# AWR2243_QSPI_Flash.net
KiCad netlist of a schematic drawn in Altium Designer
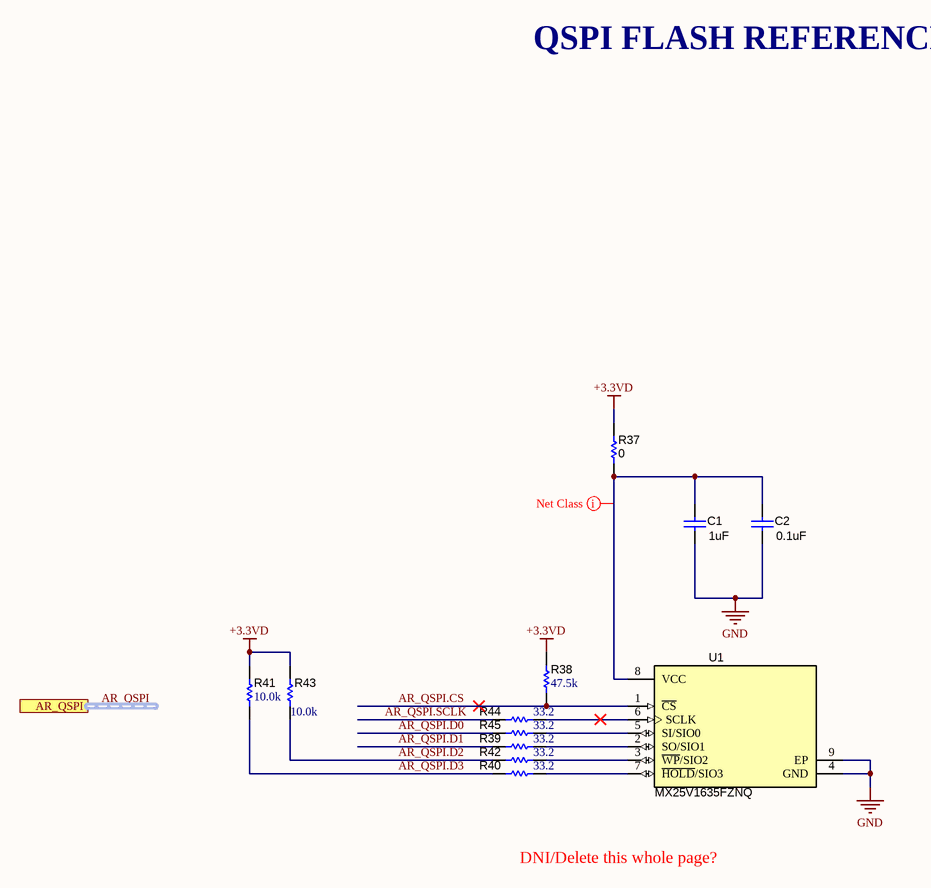
[diagram p0: AWR2243_QSPI_Flash.SchDoc]

(export (version "E")
  (design (tool "Eeschema 10.0.6"))
  (components
    (comp (ref "C1")
      (value "GCM188R71C105KA64D")
      (footprint "0603")
      (description "CAP, CERM, 1 uF, 16 V, +/- 10%, X7R, AEC-Q200 Grade 1, 0603")
      (fields
        (field (name "MANUFACTURER") "MuRata")
        (field (name "VALUEDISPLAYED") "1uF")
        (field (name "PUBLISHER") "Texas Instruments")
      )
      (libsource (lib "Altium Vault - TI") (part "Capacitor"))
    )
    (comp (ref "C2")
      (value "CGA2B3X7R1H104K050BB")
      (footprint "0402L")
      (description "CAP, CERM, 0.1 uF, 50 V, +/- 10%, X7R, AEC-Q200 Grade 1, 0402")
      (fields
        (field (name "MANUFACTURER") "TDK")
        (field (name "VALUEDISPLAYED") "0.1uF")
        (field (name "PUBLISHER") "Texas Instruments")
      )
      (libsource (lib "Altium Vault - TI") (part "Capacitor"))
    )
    (comp (ref "R37")
      (value "ERJ-2GE0R00X")
      (footprint "0402L")
      (description "RES, 0, 5%, 0.063 W, 0402")
      (fields
        (field (name "MANUFACTURER") "Panasonic")
        (field (name "VALUEDISPLAYED") "0")
        (field (name "PUBLISHER") "Texas Instruments")
      )
      (libsource (lib "Altium Vault - TI") (part "Resistor"))
    )
    (comp (ref "R38")
      (value "CRCW040247K5FKED")
      (footprint "0402L")
      (description "RES, 47.5 k, 1%, 0.063 W, AEC-Q200 Grade 0, 0402")
      (fields (field (name "MANUFACTURER") "Vishay-Dale") (field (name "VALUEDISPLAYED") "47.5k"))
      (libsource (lib "Altium Vault - TI") (part "Resistor"))
    )
    (comp (ref "R39")
      (value "CRCW020133R2FNED")
      (footprint "0201_Silk")
      (description "RES, 33.2, 1%, 0.05 W, 0201")
      (fields (field (name "MANUFACTURER") "Vishay-Dale") (field (name "VALUEDISPLAYED") "33.2"))
      (libsource (lib "Altium Vault - TI") (part "Resistor"))
    )
    (comp (ref "R40")
      (value "CRCW020133R2FNED")
      (footprint "0201_Silk")
      (description "RES, 33.2, 1%, 0.05 W, 0201")
      (fields (field (name "MANUFACTURER") "Vishay-Dale") (field (name "VALUEDISPLAYED") "33.2"))
      (libsource (lib "Altium Vault - TI") (part "Resistor"))
    )
    (comp (ref "R41")
      (value "CRCW040210K0FKED")
      (footprint "0402L")
      (description "RES, 10.0 k, 1%, 0.063 W, AEC-Q200 Grade 0, 0402")
      (fields (field (name "MANUFACTURER") "Vishay-Dale") (field (name "VALUEDISPLAYED") "10.0k"))
      (libsource (lib "Altium Vault - TI") (part "Resistor"))
    )
    (comp (ref "R42")
      (value "CRCW020133R2FNED")
      (footprint "0201_Silk")
      (description "RES, 33.2, 1%, 0.05 W, 0201")
      (fields (field (name "MANUFACTURER") "Vishay-Dale") (field (name "VALUEDISPLAYED") "33.2"))
      (libsource (lib "Altium Vault - TI") (part "Resistor"))
    )
    (comp (ref "R43")
      (value "CRCW040210K0FKED")
      (footprint "0402L")
      (description "RES, 10.0 k, 1%, 0.063 W, AEC-Q200 Grade 0, 0402")
      (fields (field (name "MANUFACTURER") "Vishay-Dale") (field (name "VALUEDISPLAYED") "10.0k"))
      (libsource (lib "Altium Vault - TI") (part "Resistor"))
    )
    (comp (ref "R44")
      (value "CRCW020133R2FNED")
      (footprint "0201_Silk")
      (description "RES, 33.2, 1%, 0.05 W, 0201")
      (fields (field (name "MANUFACTURER") "Vishay-Dale") (field (name "VALUEDISPLAYED") "33.2"))
      (libsource (lib "Altium Vault - TI") (part "Resistor"))
    )
    (comp (ref "R45")
      (value "CRCW020133R2FNED")
      (footprint "0201_Silk")
      (description "RES, 33.2, 1%, 0.05 W, 0201")
      (fields (field (name "MANUFACTURER") "Vishay-Dale") (field (name "VALUEDISPLAYED") "33.2"))
      (libsource (lib "Altium Vault - TI") (part "Resistor"))
    )
    (comp (ref "U1")
      (value "MX25V1635FZNQ")
      (footprint "WSON-8L_6x5MM_EP")
      (description "2.3V-3.6V, 16M-BIT [x 1/x 2/x 4] CMOS FLASH Memory, WSON-8")
      (fields (field (name "MANUFACTURER") "Macronix International Co., LTD"))
      (libsource (lib "Altium Vault - TI") (part "MX25V1635FZ"))
    )
  )
  (nets
    (net (code "2") (name "+3.3VD") (class "Default")
      (node (ref "R37") (pin "1") (pinfunction "1_1") (pintype "passive"))
      (node (ref "R38") (pin "2") (pinfunction "2_2") (pintype "passive"))
      (node (ref "R41") (pin "2") (pinfunction "2_2") (pintype "passive"))
      (node (ref "R43") (pin "2") (pinfunction "2_2") (pintype "passive"))
    )
    (net (code "3") (name "/AR_QSPI.CS") (class "Default")
      (node (ref "R38") (pin "1") (pinfunction "1_1") (pintype "passive"))
      (node (ref "U1") (pin "1") (pinfunction "CS_1") (pintype "input"))
    )
    (net (code "4") (name "/AR_QSPI.D0") (class "Default")
      (node (ref "R45") (pin "2") (pinfunction "2_2") (pintype "passive"))
    )
    (net (code "5") (name "/AR_QSPI.D1") (class "Default")
      (node (ref "R39") (pin "1") (pinfunction "1_1") (pintype "passive"))
    )
    (net (code "6") (name "/AR_QSPI.D2") (class "Default")
      (node (ref "R42") (pin "1") (pinfunction "1_1") (pintype "passive"))
      (node (ref "R43") (pin "1") (pinfunction "1_1") (pintype "passive"))
    )
    (net (code "7") (name "/AR_QSPI.D3") (class "Default")
      (node (ref "R40") (pin "2") (pinfunction "2_2") (pintype "passive"))
      (node (ref "R41") (pin "1") (pinfunction "1_1") (pintype "passive"))
    )
    (net (code "8") (name "/AR_QSPI.SCLK") (class "Default")
      (node (ref "R44") (pin "2") (pinfunction "2_2") (pintype "passive"))
    )
    (net (code "10") (name "GND") (class "Default")
      (node (ref "C1") (pin "1") (pinfunction "1_1") (pintype "passive"))
      (node (ref "C2") (pin "1") (pinfunction "1_1") (pintype "passive"))
      (node (ref "U1") (pin "4") (pinfunction "GND_4") (pintype "power_in"))
      (node (ref "U1") (pin "9") (pinfunction "EP_9") (pintype "passive"))
    )
    (net (code "11") (name "Net-(U1-SCLK)") (class "Default")
      (node (ref "R44") (pin "1") (pinfunction "1_1") (pintype "passive"))
      (node (ref "U1") (pin "6") (pinfunction "SCLK_6") (pintype "input"))
    )
    (net (code "12") (name "Net-(U1-SI{slash}SIO0)") (class "Default")
      (node (ref "R45") (pin "1") (pinfunction "1_1") (pintype "passive"))
      (node (ref "U1") (pin "5") (pinfunction "SI/SIO0_5") (pintype "bidirectional"))
    )
    (net (code "13") (name "Net-(U1-SO{slash}SIO1)") (class "Default")
      (node (ref "R39") (pin "2") (pinfunction "2_2") (pintype "passive"))
      (node (ref "U1") (pin "2") (pinfunction "SO/SIO1_2") (pintype "bidirectional"))
    )
    (net (code "14") (name "Net-(U1-VCC)") (class "Default")
      (node (ref "C1") (pin "2") (pinfunction "2_2") (pintype "passive"))
      (node (ref "C2") (pin "2") (pinfunction "2_2") (pintype "passive"))
      (node (ref "R37") (pin "2") (pinfunction "2_2") (pintype "passive"))
      (node (ref "U1") (pin "8") (pinfunction "VCC_8") (pintype "power_in"))
    )
    (net (code "15") (name "Net-(U1-~{HOLD}{slash}SIO3)") (class "Default")
      (node (ref "R40") (pin "1") (pinfunction "1_1") (pintype "passive"))
      (node (ref "U1") (pin "7") (pinfunction "~{HOLD}/SIO3_7") (pintype "bidirectional"))
    )
    (net (code "16") (name "Net-(U1-~{WP}{slash}SIO2)") (class "Default")
      (node (ref "R42") (pin "2") (pinfunction "2_2") (pintype "passive"))
      (node (ref "U1") (pin "3") (pinfunction "~{WP}/SIO2_3") (pintype "bidirectional"))
    )
  )
)
